# RS485_RS232_Sheet.net
KiCad netlist of a schematic drawn in Altium Designer
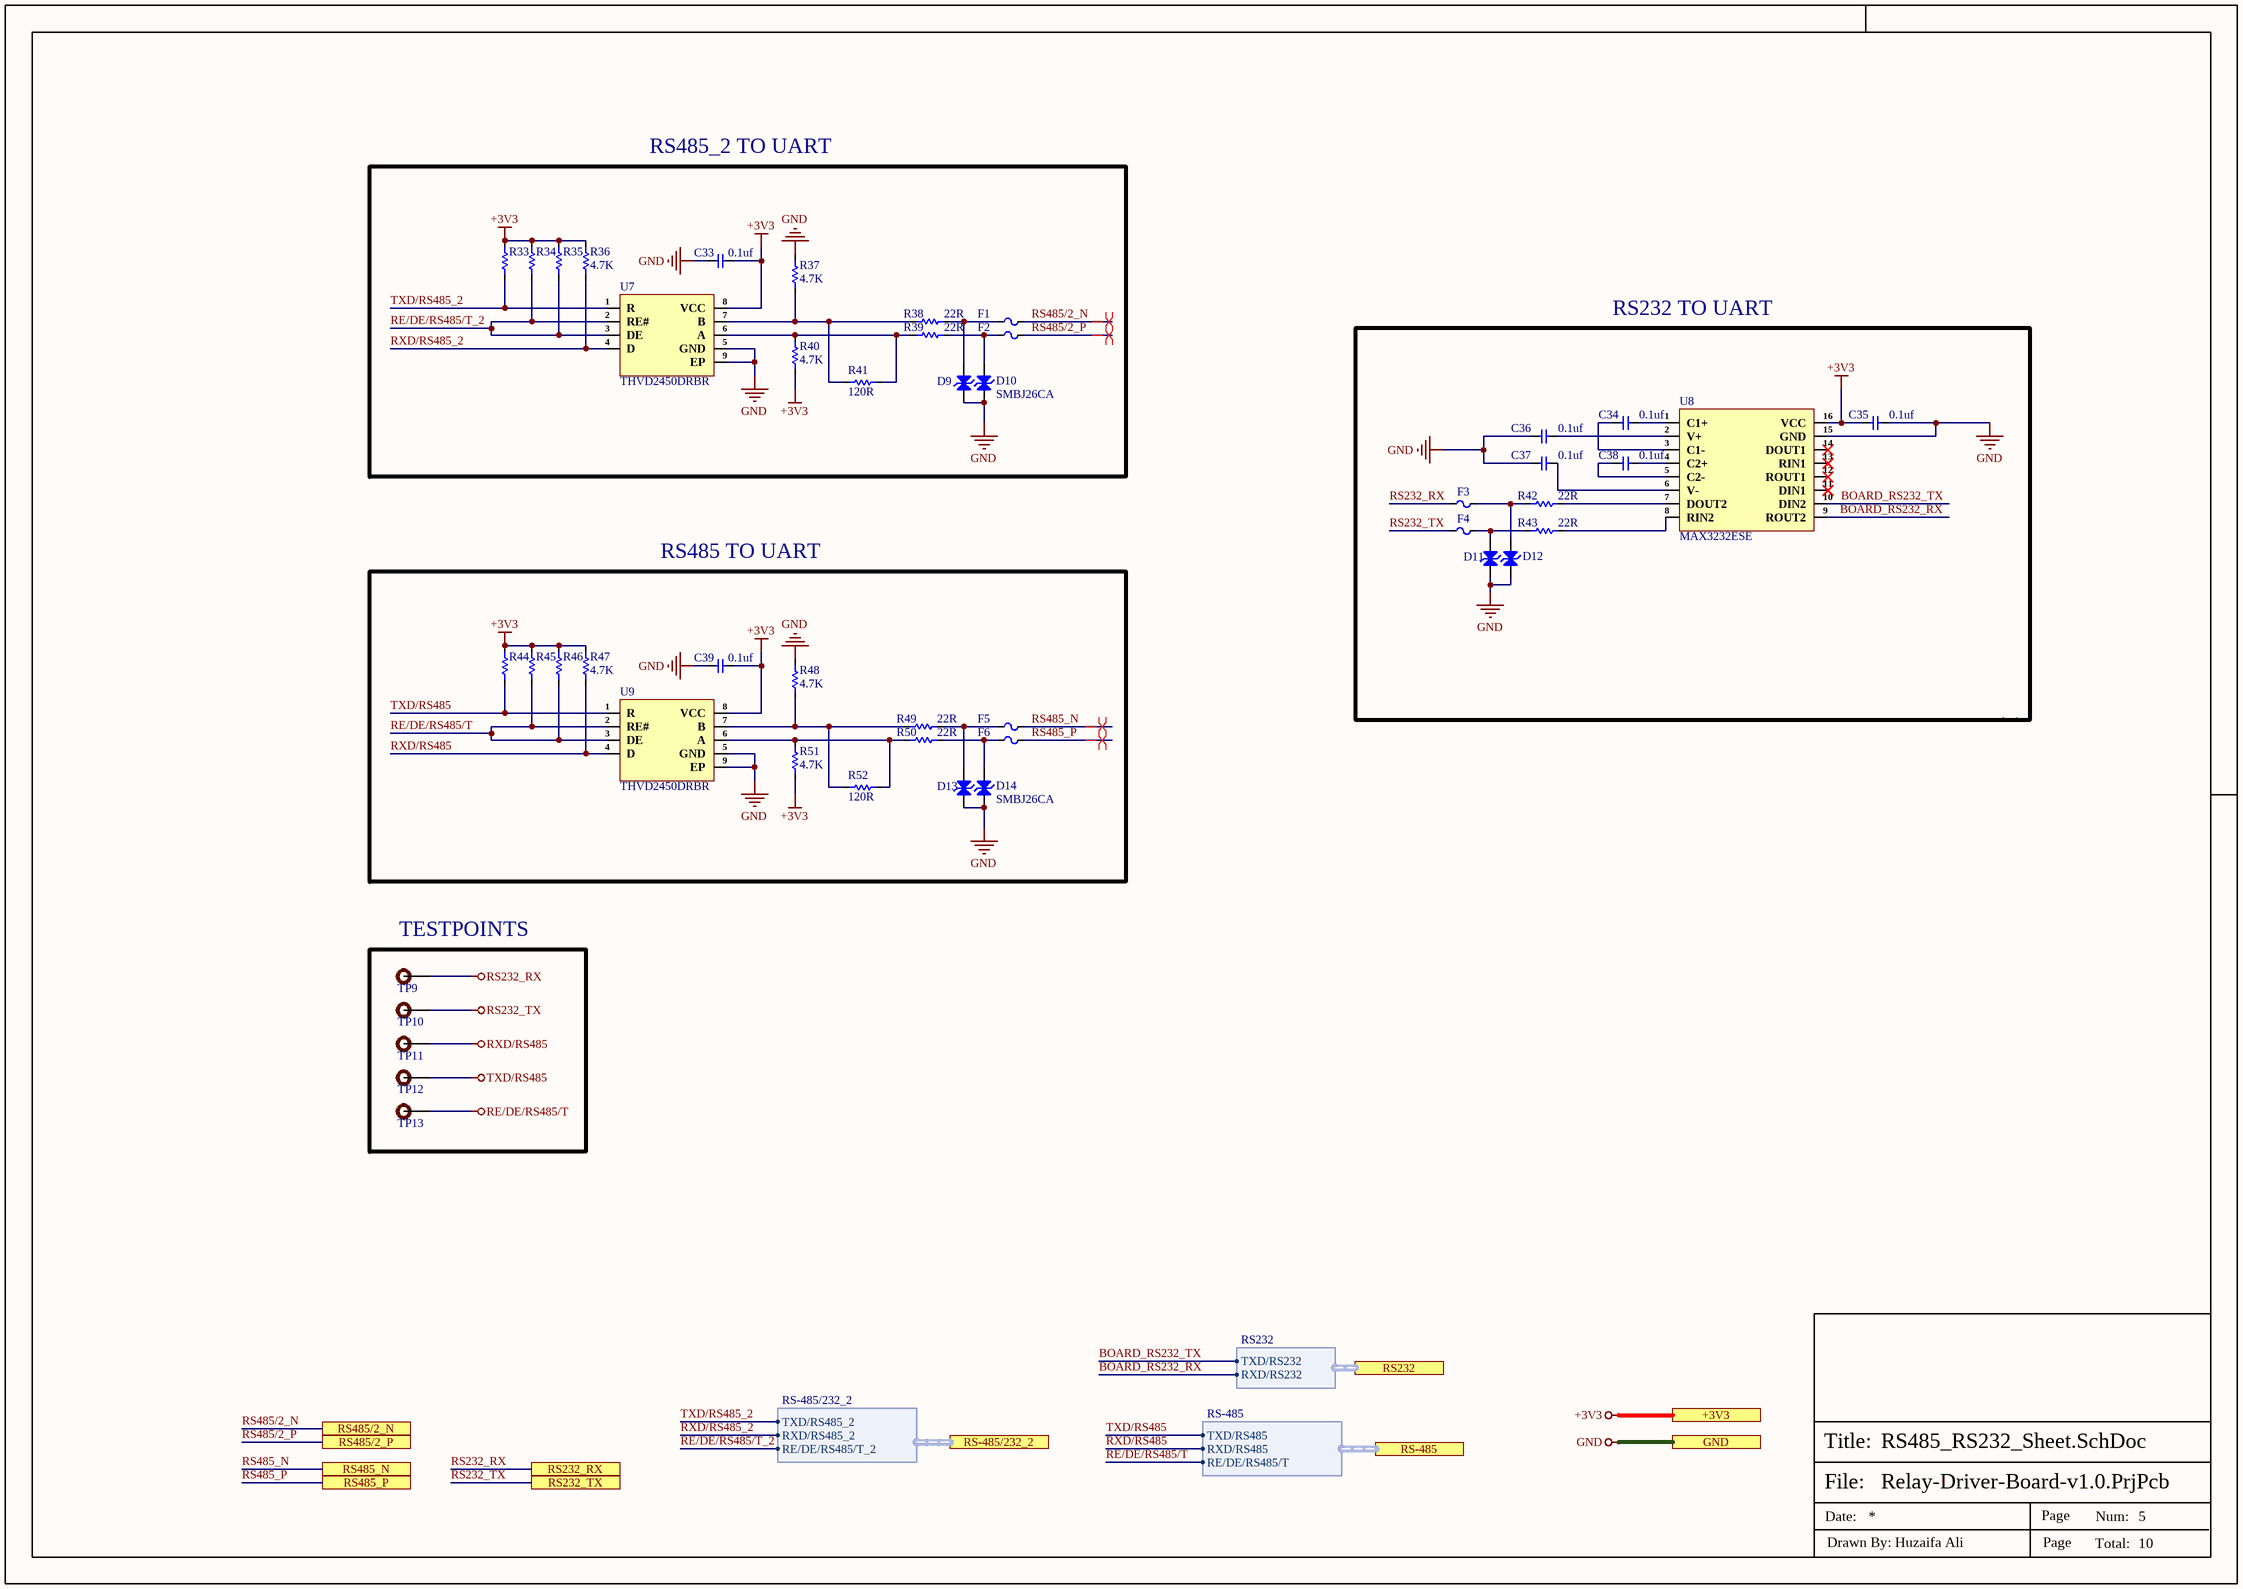
[diagram p0: RS485_RS232_Sheet.SchDoc]

(export (version "E")
  (design (tool "Eeschema 10.0.6"))
  (components
    (comp (ref "C33")
      (value "0.1uf")
      (footprint "Cap-0402")
      (description "CAP CER 0.1UF 100V X5R 0402")
      (fields
        (field (name "MANUFACTURER") "Murata")
        (field (name "MANUFACTURER PART NUMBER") "GRM155R62A104KE14D")
      )
      (libsource (lib "eSpark Libraries") (part "GRM155R62A104KE14D"))
    )
    (comp (ref "C34")
      (value "0.1uf")
      (footprint "Cap-0402")
      (description "CAP CER 0.1UF 100V X5R 0402")
      (fields
        (field (name "MANUFACTURER") "Murata")
        (field (name "MANUFACTURER PART NUMBER") "GRM155R62A104KE14D")
      )
      (libsource (lib "eSpark Libraries") (part "GRM155R62A104KE14D"))
    )
    (comp (ref "C35")
      (value "0.1uf")
      (footprint "Cap-0402")
      (description "CAP CER 0.1UF 100V X5R 0402")
      (fields
        (field (name "MANUFACTURER") "Murata")
        (field (name "MANUFACTURER PART NUMBER") "GRM155R62A104KE14D")
      )
      (libsource (lib "eSpark Libraries") (part "GRM155R62A104KE14D"))
    )
    (comp (ref "C36")
      (value "0.1uf")
      (footprint "Cap-0402")
      (description "CAP CER 0.1UF 100V X5R 0402")
      (fields
        (field (name "MANUFACTURER") "Murata")
        (field (name "MANUFACTURER PART NUMBER") "GRM155R62A104KE14D")
      )
      (libsource (lib "eSpark Libraries") (part "GRM155R62A104KE14D"))
    )
    (comp (ref "C37")
      (value "0.1uf")
      (footprint "Cap-0402")
      (description "CAP CER 0.1UF 100V X5R 0402")
      (fields
        (field (name "MANUFACTURER") "Murata")
        (field (name "MANUFACTURER PART NUMBER") "GRM155R62A104KE14D")
      )
      (libsource (lib "eSpark Libraries") (part "GRM155R62A104KE14D"))
    )
    (comp (ref "C38")
      (value "0.1uf")
      (footprint "Cap-0402")
      (description "CAP CER 0.1UF 100V X5R 0402")
      (fields
        (field (name "MANUFACTURER") "Murata")
        (field (name "MANUFACTURER PART NUMBER") "GRM155R62A104KE14D")
      )
      (libsource (lib "eSpark Libraries") (part "GRM155R62A104KE14D"))
    )
    (comp (ref "C39")
      (value "0.1uf")
      (footprint "Cap-0402")
      (description "CAP CER 0.1UF 100V X5R 0402")
      (fields
        (field (name "MANUFACTURER") "Murata")
        (field (name "MANUFACTURER PART NUMBER") "GRM155R62A104KE14D")
      )
      (libsource (lib "eSpark Libraries") (part "GRM155R62A104KE14D"))
    )
    (comp (ref "D9")
      (value "SMBJ26CA")
      (footprint "SMB Bi Directional")
      (description "SMB(DO-214AA) TVS ROHS")
      (fields (field (name "MANUFACTURER") "MSKSEMI") (field (name "LCSC PART NUMBER") "C5331111"))
      (libsource (lib "eSpark Libraries") (part "SMBJ26CA"))
    )
    (comp (ref "D10")
      (value "SMBJ26CA")
      (footprint "SMB Bi Directional")
      (description "SMB(DO-214AA) TVS ROHS")
      (fields (field (name "MANUFACTURER") "MSKSEMI") (field (name "LCSC PART NUMBER") "C5331111"))
      (libsource (lib "eSpark Libraries") (part "SMBJ26CA"))
    )
    (comp (ref "D11")
      (value "SMBJ26CA")
      (footprint "SMB Bi Directional")
      (description "SMB(DO-214AA) TVS ROHS")
      (fields (field (name "MANUFACTURER") "MSKSEMI") (field (name "LCSC PART NUMBER") "C5331111"))
      (libsource (lib "eSpark Libraries") (part "SMBJ26CA"))
    )
    (comp (ref "D12")
      (value "SMBJ26CA")
      (footprint "SMB Bi Directional")
      (description "SMB(DO-214AA) TVS ROHS")
      (fields (field (name "MANUFACTURER") "MSKSEMI") (field (name "LCSC PART NUMBER") "C5331111"))
      (libsource (lib "eSpark Libraries") (part "SMBJ26CA"))
    )
    (comp (ref "D13")
      (value "SMBJ26CA")
      (footprint "SMB Bi Directional")
      (description "SMB(DO-214AA) TVS ROHS")
      (fields (field (name "MANUFACTURER") "MSKSEMI") (field (name "LCSC PART NUMBER") "C5331111"))
      (libsource (lib "eSpark Libraries") (part "SMBJ26CA"))
    )
    (comp (ref "D14")
      (value "SMBJ26CA")
      (footprint "SMB Bi Directional")
      (description "SMB(DO-214AA) TVS ROHS")
      (fields (field (name "MANUFACTURER") "MSKSEMI") (field (name "LCSC PART NUMBER") "C5331111"))
      (libsource (lib "eSpark Libraries") (part "SMBJ26CA"))
    )
    (comp (ref "F1")
      (value "SMD0805P020TF")
      (footprint "Fuse-0805")
      (description "9V 200mA 100A 500mA 0805 Resettable Fuses ROHS")
      (fields (field (name "MANUFACTURER") "RUILON") (field (name "LCSC PART NUMBER") "C20976"))
      (libsource (lib "eSpark_centralized_Library(2022)") (part "SMD0805P020TF"))
    )
    (comp (ref "F2")
      (value "SMD0805P020TF")
      (footprint "Fuse-0805")
      (description "9V 200mA 100A 500mA 0805 Resettable Fuses ROHS")
      (fields (field (name "MANUFACTURER") "RUILON") (field (name "LCSC PART NUMBER") "C20976"))
      (libsource (lib "eSpark_centralized_Library(2022)") (part "SMD0805P020TF"))
    )
    (comp (ref "F3")
      (value "SMD0805P020TF")
      (footprint "Fuse-0805")
      (description "9V 200mA 100A 500mA 0805 Resettable Fuses ROHS")
      (fields (field (name "MANUFACTURER") "RUILON") (field (name "LCSC PART NUMBER") "C20976"))
      (libsource (lib "eSpark Libraries") (part "SMD0805P020TF"))
    )
    (comp (ref "F4")
      (value "SMD0805P020TF")
      (footprint "Fuse-0805")
      (description "9V 200mA 100A 500mA 0805 Resettable Fuses ROHS")
      (fields (field (name "MANUFACTURER") "RUILON") (field (name "LCSC PART NUMBER") "C20976"))
      (libsource (lib "eSpark Libraries") (part "SMD0805P020TF"))
    )
    (comp (ref "F5")
      (value "SMD0805P020TF")
      (footprint "Fuse-0805")
      (description "9V 200mA 100A 500mA 0805 Resettable Fuses ROHS")
      (fields (field (name "MANUFACTURER") "RUILON") (field (name "LCSC PART NUMBER") "C20976"))
      (libsource (lib "eSpark_centralized_Library(2022)") (part "SMD0805P020TF"))
    )
    (comp (ref "F6")
      (value "SMD0805P020TF")
      (footprint "Fuse-0805")
      (description "9V 200mA 100A 500mA 0805 Resettable Fuses ROHS")
      (fields (field (name "MANUFACTURER") "RUILON") (field (name "LCSC PART NUMBER") "C20976"))
      (libsource (lib "eSpark_centralized_Library(2022)") (part "SMD0805P020TF"))
    )
    (comp (ref "R33")
      (value "4.7K")
      (footprint "Res-0402")
      (description "RES 4.7K OHM 1% 1/16W 0402")
      (fields
        (field (name "MANUFACTURER") "Yageo")
        (field (name "MANUFACTURER PART NUMBER") "RC0402FR-074K7L")
      )
      (libsource (lib "eSpark Libraries") (part "RC0402FR-074K7L"))
    )
    (comp (ref "R34")
      (value "4.7K")
      (footprint "Res-0402")
      (description "RES 4.7K OHM 1% 1/16W 0402")
      (fields
        (field (name "MANUFACTURER") "Yageo")
        (field (name "MANUFACTURER PART NUMBER") "RC0402FR-074K7L")
      )
      (libsource (lib "eSpark Libraries") (part "RC0402FR-074K7L"))
    )
    (comp (ref "R35")
      (value "4.7K")
      (footprint "Res-0402")
      (description "RES 4.7K OHM 1% 1/16W 0402")
      (fields
        (field (name "MANUFACTURER") "Yageo")
        (field (name "MANUFACTURER PART NUMBER") "RC0402FR-074K7L")
      )
      (libsource (lib "eSpark Libraries") (part "RC0402FR-074K7L"))
    )
    (comp (ref "R36")
      (value "4.7K")
      (footprint "Res-0402")
      (description "RES 4.7K OHM 1% 1/16W 0402")
      (fields
        (field (name "MANUFACTURER") "Yageo")
        (field (name "MANUFACTURER PART NUMBER") "RC0402FR-074K7L")
      )
      (libsource (lib "eSpark Libraries") (part "RC0402FR-074K7L"))
    )
    (comp (ref "R37")
      (value "4.7K")
      (footprint "Res-0402")
      (description "RES 4.7K OHM 1% 1/16W 0402")
      (fields
        (field (name "MANUFACTURER") "Yageo")
        (field (name "MANUFACTURER PART NUMBER") "RC0402FR-074K7L")
      )
      (libsource (lib "eSpark Libraries") (part "RC0402FR-074K7L"))
    )
    (comp (ref "R38")
      (value "22R")
      (footprint "Res-0201")
      (description "RES 22 OHM 1% 1/20W 0201")
      (fields
        (field (name "MANUFACTURER") "Yageo")
        (field (name "MANUFACTURER PART NUMBER") "RC0201FR-0722RL")
      )
      (libsource (lib "eSpark Libraries") (part "RC0201FR-0722RL"))
    )
    (comp (ref "R39")
      (value "22R")
      (footprint "Res-0201")
      (description "RES 22 OHM 1% 1/20W 0201")
      (fields
        (field (name "MANUFACTURER") "Yageo")
        (field (name "MANUFACTURER PART NUMBER") "RC0201FR-0722RL")
      )
      (libsource (lib "eSpark Libraries") (part "RC0201FR-0722RL"))
    )
    (comp (ref "R40")
      (value "4.7K")
      (footprint "Res-0402")
      (description "RES 4.7K OHM 1% 1/16W 0402")
      (fields
        (field (name "MANUFACTURER") "Yageo")
        (field (name "MANUFACTURER PART NUMBER") "RC0402FR-074K7L")
      )
      (libsource (lib "eSpark Libraries") (part "RC0402FR-074K7L"))
    )
    (comp (ref "R41")
      (value "120R")
      (footprint "Res-0603")
      (description "RES 120 OHM 5% 1/10W 0603")
      (fields
        (field (name "MANUFACTURER") "Yageo")
        (field (name "MANUFACTURER PART NUMBER") "RC0603JR-07120RL")
      )
      (libsource (lib "eSpark Libraries") (part "RC0603JR-07120RL"))
    )
    (comp (ref "R42")
      (value "22R")
      (footprint "Res-0201")
      (description "RES 22 OHM 1% 1/20W 0201")
      (fields
        (field (name "MANUFACTURER") "Yageo")
        (field (name "MANUFACTURER PART NUMBER") "RC0201FR-0722RL")
      )
      (libsource (lib "eSpark Libraries") (part "RC0201FR-0722RL"))
    )
    (comp (ref "R43")
      (value "22R")
      (footprint "Res-0201")
      (description "RES 22 OHM 1% 1/20W 0201")
      (fields
        (field (name "MANUFACTURER") "Yageo")
        (field (name "MANUFACTURER PART NUMBER") "RC0201FR-0722RL")
      )
      (libsource (lib "eSpark Libraries") (part "RC0201FR-0722RL"))
    )
    (comp (ref "R44")
      (value "4.7K")
      (footprint "Res-0402")
      (description "RES 4.7K OHM 1% 1/16W 0402")
      (fields
        (field (name "MANUFACTURER") "Yageo")
        (field (name "MANUFACTURER PART NUMBER") "RC0402FR-074K7L")
      )
      (libsource (lib "eSpark Libraries") (part "RC0402FR-074K7L"))
    )
    (comp (ref "R45")
      (value "4.7K")
      (footprint "Res-0402")
      (description "RES 4.7K OHM 1% 1/16W 0402")
      (fields
        (field (name "MANUFACTURER") "Yageo")
        (field (name "MANUFACTURER PART NUMBER") "RC0402FR-074K7L")
      )
      (libsource (lib "eSpark Libraries") (part "RC0402FR-074K7L"))
    )
    (comp (ref "R46")
      (value "4.7K")
      (footprint "Res-0402")
      (description "RES 4.7K OHM 1% 1/16W 0402")
      (fields
        (field (name "MANUFACTURER") "Yageo")
        (field (name "MANUFACTURER PART NUMBER") "RC0402FR-074K7L")
      )
      (libsource (lib "eSpark Libraries") (part "RC0402FR-074K7L"))
    )
    (comp (ref "R47")
      (value "4.7K")
      (footprint "Res-0402")
      (description "RES 4.7K OHM 1% 1/16W 0402")
      (fields
        (field (name "MANUFACTURER") "Yageo")
        (field (name "MANUFACTURER PART NUMBER") "RC0402FR-074K7L")
      )
      (libsource (lib "eSpark Libraries") (part "RC0402FR-074K7L"))
    )
    (comp (ref "R48")
      (value "4.7K")
      (footprint "Res-0402")
      (description "RES 4.7K OHM 1% 1/16W 0402")
      (fields
        (field (name "MANUFACTURER") "Yageo")
        (field (name "MANUFACTURER PART NUMBER") "RC0402FR-074K7L")
      )
      (libsource (lib "eSpark Libraries") (part "RC0402FR-074K7L"))
    )
    (comp (ref "R49")
      (value "22R")
      (footprint "Res-0201")
      (description "RES 22 OHM 1% 1/20W 0201")
      (fields
        (field (name "MANUFACTURER") "Yageo")
        (field (name "MANUFACTURER PART NUMBER") "RC0201FR-0722RL")
      )
      (libsource (lib "eSpark Libraries") (part "RC0201FR-0722RL"))
    )
    (comp (ref "R50")
      (value "22R")
      (footprint "Res-0201")
      (description "RES 22 OHM 1% 1/20W 0201")
      (fields
        (field (name "MANUFACTURER") "Yageo")
        (field (name "MANUFACTURER PART NUMBER") "RC0201FR-0722RL")
      )
      (libsource (lib "eSpark Libraries") (part "RC0201FR-0722RL"))
    )
    (comp (ref "R51")
      (value "4.7K")
      (footprint "Res-0402")
      (description "RES 4.7K OHM 1% 1/16W 0402")
      (fields
        (field (name "MANUFACTURER") "Yageo")
        (field (name "MANUFACTURER PART NUMBER") "RC0402FR-074K7L")
      )
      (libsource (lib "eSpark Libraries") (part "RC0402FR-074K7L"))
    )
    (comp (ref "R52")
      (value "120R")
      (footprint "Res-0603")
      (description "RES 120 OHM 5% 1/10W 0603")
      (fields
        (field (name "MANUFACTURER") "Yageo")
        (field (name "MANUFACTURER PART NUMBER") "RC0603JR-07120RL")
      )
      (libsource (lib "eSpark Libraries") (part "RC0603JR-07120RL"))
    )
    (comp (ref "TP9")
      (value "TEST POINT")
      (footprint "Test-point")
      (description "Test Point ON")
      (libsource (lib "eSpark Libraries") (part "TEST POINT"))
    )
    (comp (ref "TP10")
      (value "TEST POINT")
      (footprint "Test-point")
      (description "Test Point ON")
      (libsource (lib "eSpark Libraries") (part "TEST POINT"))
    )
    (comp (ref "TP11")
      (value "TEST POINT")
      (footprint "Test-point")
      (description "Test Point ON")
      (libsource (lib "eSpark Libraries") (part "TEST POINT"))
    )
    (comp (ref "TP12")
      (value "TEST POINT")
      (footprint "Test-point")
      (description "Test Point ON")
      (libsource (lib "eSpark Libraries") (part "TEST POINT"))
    )
    (comp (ref "TP13")
      (value "TEST POINT")
      (footprint "Test-point")
      (description "Test Point ON")
      (libsource (lib "eSpark Libraries") (part "TEST POINT"))
    )
    (comp (ref "U7")
      (value "THVD2450DRBR")
      (footprint "SON-8-EP(3x3)")
      (description "IC TRANSCEIVER HALF 1/1 8SON")
      (fields (field (name "MANUFACTURER") "Texas Instruments") (field (name "LCSC PART NUMBER") "C2878080"))
      (libsource (lib "eSpark Libraries") (part "THVD2450DRBR"))
    )
    (comp (ref "U8")
      (value "MAX3232ESE")
      (footprint "SOP-16")
      (description "250Kbps transceiver 2/2 SOP-16 RS232 ICs ROHS")
      (fields (field (name "MANUFACTURER") "UMW") (field (name "LCSC PART NUMBER") "C2904738"))
      (libsource (lib "eSpark Libraries") (part "MAX3232ESE"))
    )
    (comp (ref "U9")
      (value "THVD2450DRBR")
      (footprint "SON-8-EP(3x3)")
      (description "IC TRANSCEIVER HALF 1/1 8SON")
      (fields (field (name "MANUFACTURER") "Texas Instruments") (field (name "LCSC PART NUMBER") "C2878080"))
      (libsource (lib "eSpark Libraries") (part "THVD2450DRBR"))
    )
  )
  (nets
    (net (code "4") (name "+3V3") (class "Default")
      (node (ref "C33") (pin "2") (pinfunction "2_2") (pintype "passive"))
      (node (ref "C35") (pin "2") (pinfunction "2_2") (pintype "passive"))
      (node (ref "C39") (pin "2") (pinfunction "2_2") (pintype "passive"))
      (node (ref "R33") (pin "2") (pinfunction "2_2") (pintype "passive"))
      (node (ref "R34") (pin "2") (pinfunction "2_2") (pintype "passive"))
      (node (ref "R35") (pin "2") (pinfunction "2_2") (pintype "passive"))
      (node (ref "R36") (pin "2") (pinfunction "2_2") (pintype "passive"))
      (node (ref "R40") (pin "1") (pinfunction "1_1") (pintype "passive"))
      (node (ref "R44") (pin "2") (pinfunction "2_2") (pintype "passive"))
      (node (ref "R45") (pin "2") (pinfunction "2_2") (pintype "passive"))
      (node (ref "R46") (pin "2") (pinfunction "2_2") (pintype "passive"))
      (node (ref "R47") (pin "2") (pinfunction "2_2") (pintype "passive"))
      (node (ref "R51") (pin "1") (pinfunction "1_1") (pintype "passive"))
      (node (ref "U7") (pin "8") (pinfunction "VCC_8") (pintype "passive"))
      (node (ref "U8") (pin "16") (pinfunction "VCC_16") (pintype "passive"))
      (node (ref "U9") (pin "8") (pinfunction "VCC_8") (pintype "passive"))
    )
    (net (code "5") (name "/BOARD_RS232_RX") (class "Default")
      (node (ref "U8") (pin "9") (pinfunction "ROUT2_9") (pintype "passive"))
    )
    (net (code "6") (name "/BOARD_RS232_TX") (class "Default")
      (node (ref "U8") (pin "10") (pinfunction "DIN2_10") (pintype "passive"))
    )
    (net (code "7") (name "/RE{slash}DE{slash}RS485{slash}T_2") (class "Default")
      (node (ref "R34") (pin "1") (pinfunction "1_1") (pintype "passive"))
      (node (ref "R35") (pin "1") (pinfunction "1_1") (pintype "passive"))
      (node (ref "U7") (pin "2") (pinfunction "RE#_2") (pintype "passive"))
      (node (ref "U7") (pin "3") (pinfunction "DE_3") (pintype "passive"))
    )
    (net (code "8") (name "/RS485_N") (class "Default")
      (node (ref "F5") (pin "2") (pinfunction "2_2") (pintype "passive"))
    )
    (net (code "9") (name "/RS485_P") (class "Default")
      (node (ref "F6") (pin "2") (pinfunction "2_2") (pintype "passive"))
    )
    (net (code "10") (name "/RS485{slash}2_N") (class "Default")
      (node (ref "F1") (pin "2") (pinfunction "2_2") (pintype "passive"))
    )
    (net (code "11") (name "/RS485{slash}2_P") (class "Default")
      (node (ref "F2") (pin "2") (pinfunction "2_2") (pintype "passive"))
    )
    (net (code "12") (name "/RXD{slash}RS485_2") (class "Default")
      (node (ref "R36") (pin "1") (pinfunction "1_1") (pintype "passive"))
      (node (ref "U7") (pin "4") (pinfunction "D_4") (pintype "passive"))
    )
    (net (code "13") (name "/TXD{slash}RS485_2") (class "Default")
      (node (ref "R33") (pin "1") (pinfunction "1_1") (pintype "passive"))
      (node (ref "U7") (pin "1") (pinfunction "R_1") (pintype "passive"))
    )
    (net (code "17") (name "GND") (class "Default")
      (node (ref "C33") (pin "1") (pinfunction "1_1") (pintype "passive"))
      (node (ref "C35") (pin "1") (pinfunction "1_1") (pintype "passive"))
      (node (ref "C36") (pin "1") (pinfunction "1_1") (pintype "passive"))
      (node (ref "C37") (pin "1") (pinfunction "1_1") (pintype "passive"))
      (node (ref "C39") (pin "1") (pinfunction "1_1") (pintype "passive"))
      (node (ref "D10") (pin "1") (pinfunction "A_1") (pintype "passive"))
      (node (ref "D11") (pin "1") (pinfunction "A_1") (pintype "passive"))
      (node (ref "D12") (pin "1") (pinfunction "A_1") (pintype "passive"))
      (node (ref "D13") (pin "1") (pinfunction "A_1") (pintype "passive"))
      (node (ref "D14") (pin "1") (pinfunction "A_1") (pintype "passive"))
      (node (ref "D9") (pin "1") (pinfunction "A_1") (pintype "passive"))
      (node (ref "R37") (pin "2") (pinfunction "2_2") (pintype "passive"))
      (node (ref "R48") (pin "2") (pinfunction "2_2") (pintype "passive"))
      (node (ref "U7") (pin "5") (pinfunction "GND_5") (pintype "passive"))
      (node (ref "U7") (pin "9") (pinfunction "EP_9") (pintype "passive"))
      (node (ref "U8") (pin "15") (pinfunction "GND_15") (pintype "passive"))
      (node (ref "U9") (pin "5") (pinfunction "GND_5") (pintype "passive"))
      (node (ref "U9") (pin "9") (pinfunction "EP_9") (pintype "passive"))
    )
    (net (code "18") (name "Net-(D9-K)") (class "Default")
      (node (ref "D9") (pin "2") (pinfunction "K_2") (pintype "passive"))
      (node (ref "F1") (pin "1") (pinfunction "1_1") (pintype "passive"))
      (node (ref "R38") (pin "2") (pinfunction "2_2") (pintype "passive"))
    )
    (net (code "19") (name "Net-(D10-K)") (class "Default")
      (node (ref "D10") (pin "2") (pinfunction "K_2") (pintype "passive"))
      (node (ref "F2") (pin "1") (pinfunction "1_1") (pintype "passive"))
      (node (ref "R39") (pin "2") (pinfunction "2_2") (pintype "passive"))
    )
    (net (code "20") (name "Net-(D11-K)") (class "Default")
      (node (ref "D11") (pin "2") (pinfunction "K_2") (pintype "passive"))
      (node (ref "F4") (pin "2") (pinfunction "2_2") (pintype "passive"))
      (node (ref "R43") (pin "1") (pinfunction "1_1") (pintype "passive"))
    )
    (net (code "21") (name "Net-(D12-K)") (class "Default")
      (node (ref "D12") (pin "2") (pinfunction "K_2") (pintype "passive"))
      (node (ref "F3") (pin "2") (pinfunction "2_2") (pintype "passive"))
      (node (ref "R42") (pin "1") (pinfunction "1_1") (pintype "passive"))
    )
    (net (code "22") (name "Net-(D13-K)") (class "Default")
      (node (ref "D13") (pin "2") (pinfunction "K_2") (pintype "passive"))
      (node (ref "F5") (pin "1") (pinfunction "1_1") (pintype "passive"))
      (node (ref "R49") (pin "2") (pinfunction "2_2") (pintype "passive"))
    )
    (net (code "23") (name "Net-(D14-K)") (class "Default")
      (node (ref "D14") (pin "2") (pinfunction "K_2") (pintype "passive"))
      (node (ref "F6") (pin "1") (pinfunction "1_1") (pintype "passive"))
      (node (ref "R50") (pin "2") (pinfunction "2_2") (pintype "passive"))
    )
    (net (code "24") (name "Net-(U7-A)") (class "Default")
      (node (ref "R39") (pin "1") (pinfunction "1_1") (pintype "passive"))
      (node (ref "R40") (pin "2") (pinfunction "2_2") (pintype "passive"))
      (node (ref "R41") (pin "2") (pinfunction "2_2") (pintype "passive"))
      (node (ref "U7") (pin "6") (pinfunction "A_6") (pintype "passive"))
    )
    (net (code "25") (name "Net-(U7-B)") (class "Default")
      (node (ref "R37") (pin "1") (pinfunction "1_1") (pintype "passive"))
      (node (ref "R38") (pin "1") (pinfunction "1_1") (pintype "passive"))
      (node (ref "R41") (pin "1") (pinfunction "1_1") (pintype "passive"))
      (node (ref "U7") (pin "7") (pinfunction "B_7") (pintype "passive"))
    )
    (net (code "26") (name "Net-(U8-C1+)") (class "Default")
      (node (ref "C34") (pin "1") (pinfunction "1_1") (pintype "passive"))
      (node (ref "U8") (pin "1") (pinfunction "C1+_1") (pintype "passive"))
    )
    (net (code "27") (name "Net-(U8-C1-)") (class "Default")
      (node (ref "C34") (pin "2") (pinfunction "2_2") (pintype "passive"))
      (node (ref "U8") (pin "3") (pinfunction "C1-_3") (pintype "passive"))
    )
    (net (code "28") (name "Net-(U8-C2+)") (class "Default")
      (node (ref "C38") (pin "1") (pinfunction "1_1") (pintype "passive"))
      (node (ref "U8") (pin "4") (pinfunction "C2+_4") (pintype "passive"))
    )
    (net (code "29") (name "Net-(U8-C2-)") (class "Default")
      (node (ref "C38") (pin "2") (pinfunction "2_2") (pintype "passive"))
      (node (ref "U8") (pin "5") (pinfunction "C2-_5") (pintype "passive"))
    )
    (net (code "30") (name "Net-(U8-DOUT2)") (class "Default")
      (node (ref "R42") (pin "2") (pinfunction "2_2") (pintype "passive"))
      (node (ref "U8") (pin "7") (pinfunction "DOUT2_7") (pintype "passive"))
    )
    (net (code "31") (name "Net-(U8-RIN2)") (class "Default")
      (node (ref "R43") (pin "2") (pinfunction "2_2") (pintype "passive"))
      (node (ref "U8") (pin "8") (pinfunction "RIN2_8") (pintype "passive"))
    )
    (net (code "32") (name "Net-(U8-V+)") (class "Default")
      (node (ref "C36") (pin "2") (pinfunction "2_2") (pintype "passive"))
      (node (ref "U8") (pin "2") (pinfunction "V+_2") (pintype "passive"))
    )
    (net (code "33") (name "Net-(U8-V-)") (class "Default")
      (node (ref "C37") (pin "2") (pinfunction "2_2") (pintype "passive"))
      (node (ref "U8") (pin "6") (pinfunction "V-_6") (pintype "passive"))
    )
    (net (code "34") (name "Net-(U9-A)") (class "Default")
      (node (ref "R50") (pin "1") (pinfunction "1_1") (pintype "passive"))
      (node (ref "R51") (pin "2") (pinfunction "2_2") (pintype "passive"))
      (node (ref "R52") (pin "2") (pinfunction "2_2") (pintype "passive"))
      (node (ref "U9") (pin "6") (pinfunction "A_6") (pintype "passive"))
    )
    (net (code "35") (name "Net-(U9-B)") (class "Default")
      (node (ref "R48") (pin "1") (pinfunction "1_1") (pintype "passive"))
      (node (ref "R49") (pin "1") (pinfunction "1_1") (pintype "passive"))
      (node (ref "R52") (pin "1") (pinfunction "1_1") (pintype "passive"))
      (node (ref "U9") (pin "7") (pinfunction "B_7") (pintype "passive"))
    )
    (net (code "36") (name "RE{slash}DE{slash}RS485{slash}T") (class "Default")
      (node (ref "R45") (pin "1") (pinfunction "1_1") (pintype "passive"))
      (node (ref "R46") (pin "1") (pinfunction "1_1") (pintype "passive"))
      (node (ref "TP13") (pin "1") (pinfunction "1_1") (pintype "passive"))
      (node (ref "U9") (pin "2") (pinfunction "RE#_2") (pintype "passive"))
      (node (ref "U9") (pin "3") (pinfunction "DE_3") (pintype "passive"))
    )
    (net (code "37") (name "RS232_RX") (class "Default")
      (node (ref "F3") (pin "1") (pinfunction "1_1") (pintype "passive"))
      (node (ref "TP9") (pin "1") (pinfunction "1_1") (pintype "passive"))
    )
    (net (code "38") (name "RS232_TX") (class "Default")
      (node (ref "F4") (pin "1") (pinfunction "1_1") (pintype "passive"))
      (node (ref "TP10") (pin "1") (pinfunction "1_1") (pintype "passive"))
    )
    (net (code "39") (name "RXD{slash}RS485") (class "Default")
      (node (ref "R47") (pin "1") (pinfunction "1_1") (pintype "passive"))
      (node (ref "TP11") (pin "1") (pinfunction "1_1") (pintype "passive"))
      (node (ref "U9") (pin "4") (pinfunction "D_4") (pintype "passive"))
    )
    (net (code "40") (name "TXD{slash}RS485") (class "Default")
      (node (ref "R44") (pin "1") (pinfunction "1_1") (pintype "passive"))
      (node (ref "TP12") (pin "1") (pinfunction "1_1") (pintype "passive"))
      (node (ref "U9") (pin "1") (pinfunction "R_1") (pintype "passive"))
    )
    (net (code "41") (name "unconnected-(U8-DIN1-Pad11)") (class "Default")
      (node (ref "U8") (pin "11") (pinfunction "DIN1_11") (pintype "passive+no_connect"))
    )
    (net (code "42") (name "unconnected-(U8-DOUT1-Pad14)") (class "Default")
      (node (ref "U8") (pin "14") (pinfunction "DOUT1_14") (pintype "passive+no_connect"))
    )
    (net (code "43") (name "unconnected-(U8-RIN1-Pad13)") (class "Default")
      (node (ref "U8") (pin "13") (pinfunction "RIN1_13") (pintype "passive+no_connect"))
    )
    (net (code "44") (name "unconnected-(U8-ROUT1-Pad12)") (class "Default")
      (node (ref "U8") (pin "12") (pinfunction "ROUT1_12") (pintype "passive+no_connect"))
    )
  )
)
